# digidice_TI.net
KiCad netlist of a schematic drawn in EAGLE
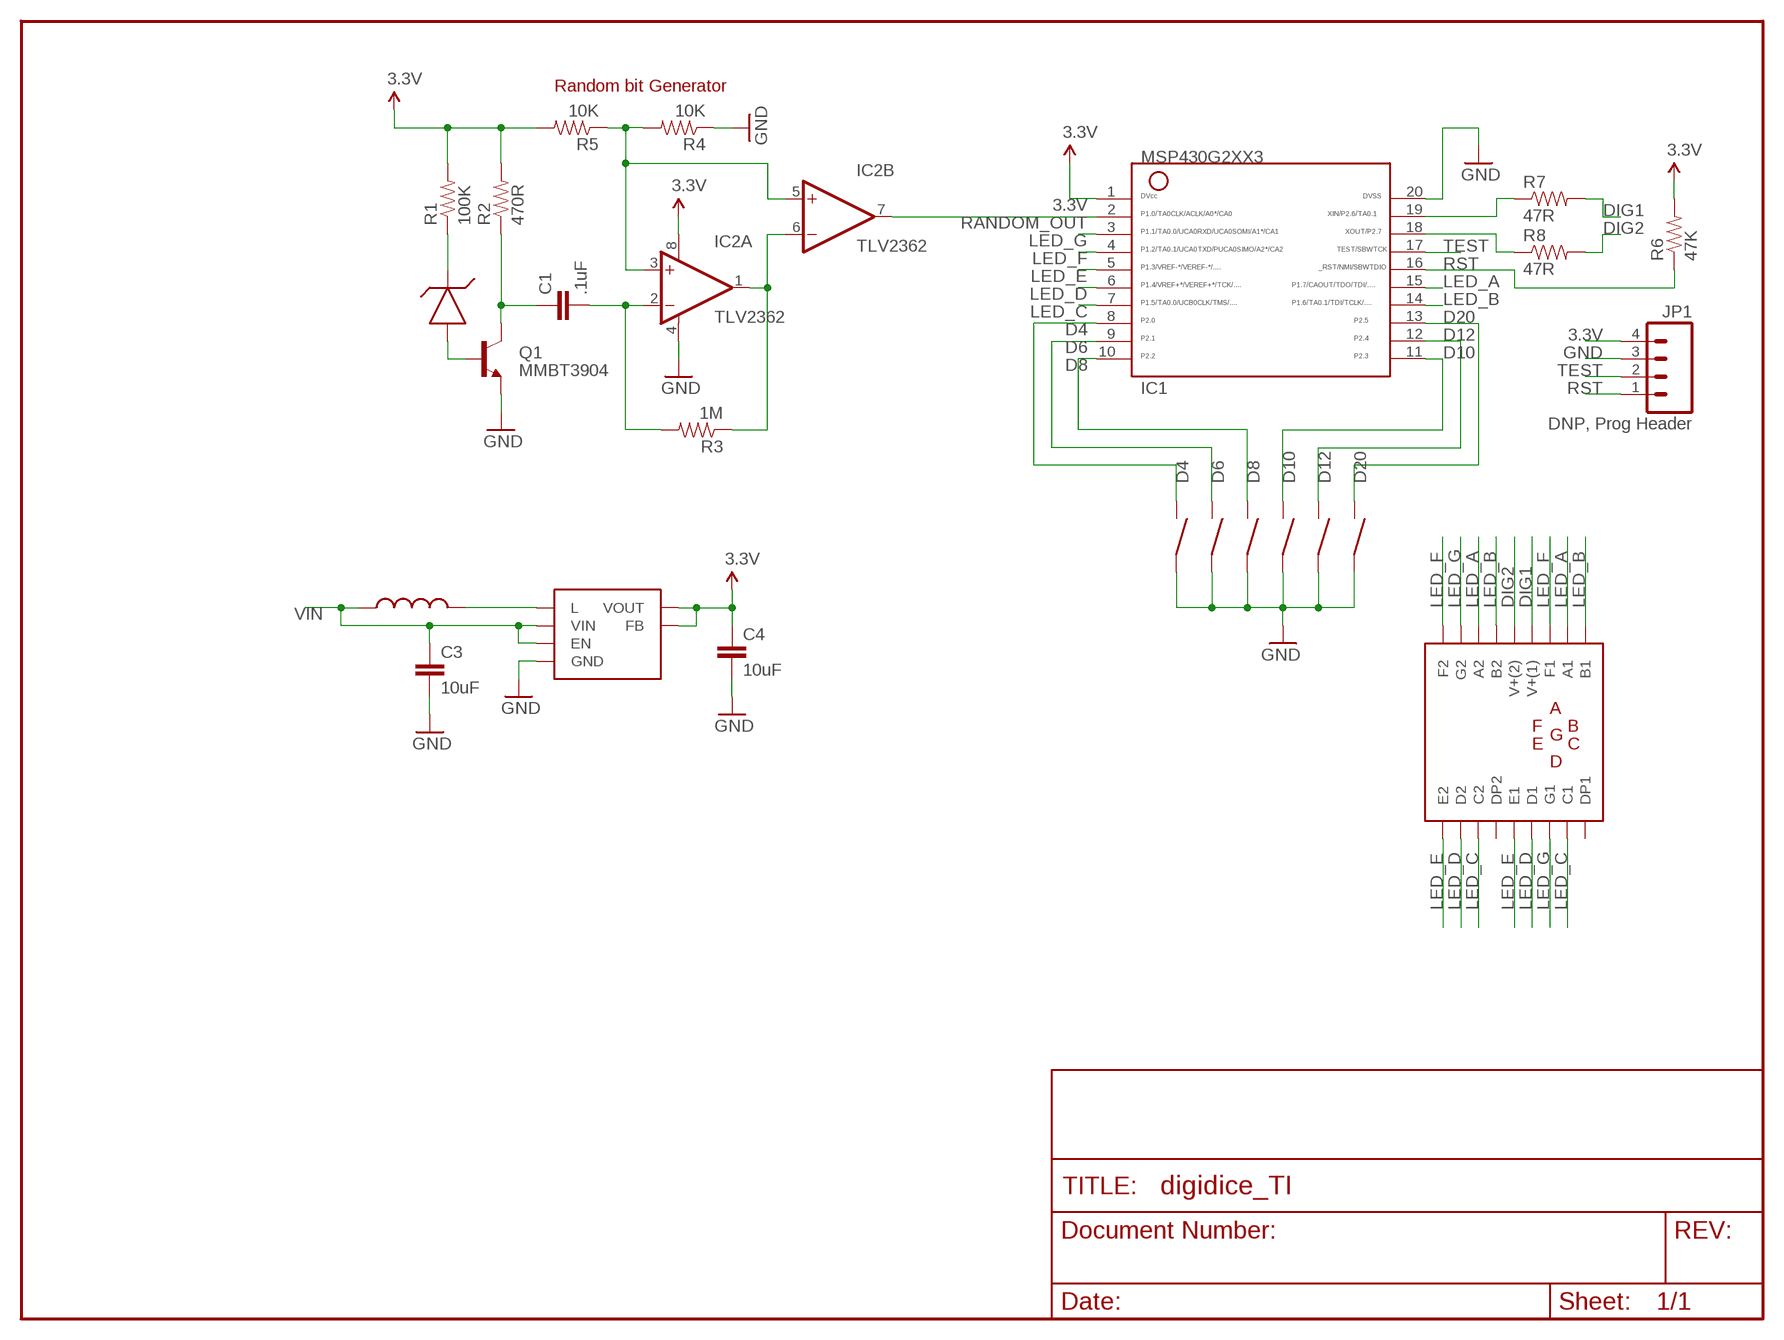
[diagram p0: schematic, sheet 1]

(export (version "E")
  (design (tool "Eeschema 10.0.6"))
  (components
    (comp (ref "C1")
      (value ".1uF")
      (footprint "eagle-import:0402-CAP")
      (libsource (lib "eagle-import") (part "CAP0402-CAP"))
    )
    (comp (ref "C3")
      (value "10uF")
      (footprint "eagle-import:0603-CAP")
      (libsource (lib "eagle-import") (part "CAP0603-CAP"))
    )
    (comp (ref "C4")
      (value "10uF")
      (footprint "eagle-import:0603-CAP")
      (libsource (lib "eagle-import") (part "CAP0603-CAP"))
    )
    (comp (ref "IC1")
      (value "MSP430G2203IPW20")
      (footprint "eagle-import:PW20")
      (libsource (lib "eagle-import") (part "G2XX3---PW20"))
    )
    (comp (ref "IC2")
      (value "TLV2362")
      (footprint "eagle-import:MSOP08")
      (fields
        (field (name "MF") "TEXAS INSTRUMENTS")
        (field (name "MPN") "OPA2340EA/250")
        (field (name "MPN_1") "OPA2340EA/250")
        (field (name "OC_FARNELL") "1101540")
        (field (name "OC_NEWARK") "36K7580")
      )
      (libsource (lib "eagle-import") (part "OPA2340E"))
    )
    (comp (ref "IC3")
      (value "TLV61225")
      (footprint "eagle-import:SOT-363")
      (libsource (lib "eagle-import") (part "TLV61225"))
    )
    (comp (ref "JP1")
      (value "DNP, Prog Header")
      (footprint "eagle-import:1X04-1.27MM")
      (libsource (lib "eagle-import") (part "M041.27MM"))
    )
    (comp (ref "L1")
      (value "PFL2015-472ML")
      (footprint "eagle-import:COILCRAFT-PFL2015")
      (libsource (lib "eagle-import") (part "INDUCTORPFL2015"))
    )
    (comp (ref "Q1")
      (value "MMBT3904")
      (footprint "eagle-import:SOT23")
      (libsource (lib "eagle-import") (part "TRANSISTOR_NPNSOT23"))
    )
    (comp (ref "R1")
      (value "100K")
      (footprint "eagle-import:0402-RES")
      (libsource (lib "eagle-import") (part "RESISTOR0402-RES"))
    )
    (comp (ref "R2")
      (value "470R")
      (footprint "eagle-import:0402-RES")
      (libsource (lib "eagle-import") (part "RESISTOR0402-RES"))
    )
    (comp (ref "R3")
      (value "1M")
      (footprint "eagle-import:0402-RES")
      (libsource (lib "eagle-import") (part "RESISTOR0402-RES"))
    )
    (comp (ref "R4")
      (value "10K")
      (footprint "eagle-import:0402-RES")
      (libsource (lib "eagle-import") (part "RESISTOR0402-RES"))
    )
    (comp (ref "R5")
      (value "10K")
      (footprint "eagle-import:0402-RES")
      (libsource (lib "eagle-import") (part "RESISTOR0402-RES"))
    )
    (comp (ref "R6")
      (value "47K")
      (footprint "eagle-import:0402-RES")
      (libsource (lib "eagle-import") (part "RESISTOR0402-RES"))
    )
    (comp (ref "R7")
      (value "47R")
      (footprint "eagle-import:0805")
      (libsource (lib "eagle-import") (part "RESISTOR"))
    )
    (comp (ref "R8")
      (value "47R")
      (footprint "eagle-import:0805")
      (libsource (lib "eagle-import") (part "RESISTOR"))
    )
    (comp (ref "SW1")
      (value "SPST_SWITCH")
      (footprint "eagle-import:EG2513-ND")
      (libsource (lib "eagle-import") (part "SPST_SWITCH"))
    )
    (comp (ref "SW2")
      (value "SPST_SWITCH")
      (footprint "eagle-import:EG2513-ND")
      (libsource (lib "eagle-import") (part "SPST_SWITCH"))
    )
    (comp (ref "SW3")
      (value "SPST_SWITCH")
      (footprint "eagle-import:EG2513-ND")
      (libsource (lib "eagle-import") (part "SPST_SWITCH"))
    )
    (comp (ref "SW4")
      (value "SPST_SWITCH")
      (footprint "eagle-import:EG2513-ND")
      (libsource (lib "eagle-import") (part "SPST_SWITCH"))
    )
    (comp (ref "SW5")
      (value "SPST_SWITCH")
      (footprint "eagle-import:EG2513-ND")
      (libsource (lib "eagle-import") (part "SPST_SWITCH"))
    )
    (comp (ref "SW6")
      (value "SPST_SWITCH")
      (footprint "eagle-import:EG2513-ND")
      (libsource (lib "eagle-import") (part "SPST_SWITCH"))
    )
    (comp (ref "U$1")
      (value "ZXRE1004FFTA")
      (footprint "eagle-import:SOT23")
      (libsource (lib "eagle-import") (part "ZXRE1004FFTA"))
    )
    (comp (ref "U$2")
      (value "2DIGIT_7SEGMENT")
      (footprint "eagle-import:HDSP-521E")
      (libsource (lib "eagle-import") (part "2DIGIT_7SEGMENT"))
    )
  )
  (nets
    (net (code "1") (name "/D4") (class "Default")
      (node (ref "IC1") (pin "8") (pinfunction "8_8") (pintype "bidirectional"))
      (node (ref "SW6") (pin "P$2") (pinfunction "2_P$2") (pintype "bidirectional"))
    )
    (net (code "2") (name "/D6") (class "Default")
      (node (ref "IC1") (pin "9") (pinfunction "9_9") (pintype "bidirectional"))
      (node (ref "SW5") (pin "P$2") (pinfunction "2_P$2") (pintype "bidirectional"))
    )
    (net (code "3") (name "/D8") (class "Default")
      (node (ref "IC1") (pin "10") (pinfunction "10_10") (pintype "bidirectional"))
      (node (ref "SW4") (pin "P$2") (pinfunction "2_P$2") (pintype "bidirectional"))
    )
    (net (code "4") (name "/D10") (class "Default")
      (node (ref "IC1") (pin "11") (pinfunction "11_11") (pintype "bidirectional"))
      (node (ref "SW3") (pin "P$2") (pinfunction "2_P$2") (pintype "bidirectional"))
    )
    (net (code "5") (name "/D12") (class "Default")
      (node (ref "IC1") (pin "12") (pinfunction "12_12") (pintype "bidirectional"))
      (node (ref "SW2") (pin "P$2") (pinfunction "2_P$2") (pintype "bidirectional"))
    )
    (net (code "6") (name "/D20") (class "Default")
      (node (ref "IC1") (pin "13") (pinfunction "13_13") (pintype "bidirectional"))
      (node (ref "SW1") (pin "P$2") (pinfunction "2_P$2") (pintype "bidirectional"))
    )
    (net (code "7") (name "/DIG1") (class "Default")
      (node (ref "R7") (pin "2") (pinfunction "2_2") (pintype "passive"))
      (node (ref "U$2") (pin "P$13") (pinfunction "V+(1)_P$13") (pintype "bidirectional"))
    )
    (net (code "8") (name "/DIG2") (class "Default")
      (node (ref "R8") (pin "2") (pinfunction "2_2") (pintype "passive"))
      (node (ref "U$2") (pin "P$14") (pinfunction "V+(2)_P$14") (pintype "bidirectional"))
    )
    (net (code "9") (name "/LED_A") (class "Default")
      (node (ref "IC1") (pin "15") (pinfunction "15_15") (pintype "bidirectional"))
      (node (ref "U$2") (pin "P$11") (pinfunction "A1_P$11") (pintype "bidirectional"))
      (node (ref "U$2") (pin "P$16") (pinfunction "A2_P$16") (pintype "bidirectional"))
    )
    (net (code "10") (name "/LED_B") (class "Default")
      (node (ref "IC1") (pin "14") (pinfunction "14_14") (pintype "bidirectional"))
      (node (ref "U$2") (pin "P$10") (pinfunction "B1_P$10") (pintype "bidirectional"))
      (node (ref "U$2") (pin "P$15") (pinfunction "B2_P$15") (pintype "bidirectional"))
    )
    (net (code "11") (name "/LED_C") (class "Default")
      (node (ref "IC1") (pin "7") (pinfunction "7_7") (pintype "bidirectional"))
      (node (ref "U$2") (pin "P$3") (pinfunction "C2_P$3") (pintype "bidirectional"))
      (node (ref "U$2") (pin "P$8") (pinfunction "C1_P$8") (pintype "bidirectional"))
    )
    (net (code "12") (name "/LED_D") (class "Default")
      (node (ref "IC1") (pin "6") (pinfunction "6_6") (pintype "bidirectional"))
      (node (ref "U$2") (pin "P$2") (pinfunction "D2_P$2") (pintype "bidirectional"))
      (node (ref "U$2") (pin "P$6") (pinfunction "D1_P$6") (pintype "bidirectional"))
    )
    (net (code "13") (name "/LED_E") (class "Default")
      (node (ref "IC1") (pin "5") (pinfunction "5_5") (pintype "bidirectional"))
      (node (ref "U$2") (pin "P$1") (pinfunction "E2_P$1") (pintype "bidirectional"))
      (node (ref "U$2") (pin "P$5") (pinfunction "E1_P$5") (pintype "bidirectional"))
    )
    (net (code "14") (name "/LED_F") (class "Default")
      (node (ref "IC1") (pin "4") (pinfunction "4_4") (pintype "bidirectional"))
      (node (ref "U$2") (pin "P$12") (pinfunction "F1_P$12") (pintype "bidirectional"))
      (node (ref "U$2") (pin "P$18") (pinfunction "F2_P$18") (pintype "bidirectional"))
    )
    (net (code "15") (name "/LED_G") (class "Default")
      (node (ref "IC1") (pin "3") (pinfunction "3_3") (pintype "bidirectional"))
      (node (ref "U$2") (pin "P$17") (pinfunction "G2_P$17") (pintype "bidirectional"))
      (node (ref "U$2") (pin "P$7") (pinfunction "G1_P$7") (pintype "bidirectional"))
    )
    (net (code "16") (name "/RANDOM_OUT") (class "Default")
      (node (ref "IC1") (pin "2") (pinfunction "2_2") (pintype "bidirectional"))
      (node (ref "IC2") (pin "7") (pinfunction "OUT_7") (pintype "output"))
    )
    (net (code "17") (name "/RST") (class "Default")
      (node (ref "IC1") (pin "16") (pinfunction "16_16") (pintype "bidirectional"))
      (node (ref "JP1") (pin "1") (pinfunction "1_1") (pintype "passive"))
      (node (ref "R6") (pin "1") (pinfunction "1_1") (pintype "passive"))
    )
    (net (code "18") (name "/TEST") (class "Default")
      (node (ref "IC1") (pin "17") (pinfunction "17_17") (pintype "bidirectional"))
      (node (ref "JP1") (pin "2") (pinfunction "2_2") (pintype "passive"))
    )
    (net (code "19") (name "/VIN") (class "Default")
      (node (ref "C3") (pin "1") (pinfunction "1_1") (pintype "passive"))
      (node (ref "IC3") (pin "P$1") (pinfunction "VIN_P$1") (pintype "bidirectional"))
      (node (ref "IC3") (pin "P$6") (pinfunction "EN_P$6") (pintype "bidirectional"))
      (node (ref "L1") (pin "P$1") (pinfunction "1_P$1") (pintype "bidirectional"))
    )
    (net (code "20") (name "3.3V") (class "Default")
      (node (ref "C4") (pin "1") (pinfunction "1_1") (pintype "passive"))
      (node (ref "IC1") (pin "1") (pinfunction "1_1") (pintype "bidirectional"))
      (node (ref "IC2") (pin "8") (pinfunction "V+_8") (pintype "power_in"))
      (node (ref "IC3") (pin "P$2") (pinfunction "FB_P$2") (pintype "bidirectional"))
      (node (ref "IC3") (pin "P$4") (pinfunction "VOUT_P$4") (pintype "bidirectional"))
      (node (ref "JP1") (pin "4") (pinfunction "4_4") (pintype "passive"))
      (node (ref "R1") (pin "2") (pinfunction "2_2") (pintype "passive"))
      (node (ref "R2") (pin "2") (pinfunction "2_2") (pintype "passive"))
      (node (ref "R5") (pin "2") (pinfunction "2_2") (pintype "passive"))
      (node (ref "R6") (pin "2") (pinfunction "2_2") (pintype "passive"))
    )
    (net (code "21") (name "GND") (class "Default")
      (node (ref "C3") (pin "2") (pinfunction "2_2") (pintype "passive"))
      (node (ref "C4") (pin "2") (pinfunction "2_2") (pintype "passive"))
      (node (ref "IC1") (pin "20") (pinfunction "20_20") (pintype "bidirectional"))
      (node (ref "IC2") (pin "4") (pinfunction "V-_4") (pintype "power_in"))
      (node (ref "IC3") (pin "P$3") (pinfunction "GND_P$3") (pintype "bidirectional"))
      (node (ref "JP1") (pin "3") (pinfunction "3_3") (pintype "passive"))
      (node (ref "Q1") (pin "2") (pinfunction "E_2") (pintype "passive"))
      (node (ref "R4") (pin "1") (pinfunction "1_1") (pintype "passive"))
      (node (ref "SW1") (pin "P$1") (pinfunction "1_P$1") (pintype "bidirectional"))
      (node (ref "SW2") (pin "P$1") (pinfunction "1_P$1") (pintype "bidirectional"))
      (node (ref "SW3") (pin "P$1") (pinfunction "1_P$1") (pintype "bidirectional"))
      (node (ref "SW4") (pin "P$1") (pinfunction "1_P$1") (pintype "bidirectional"))
      (node (ref "SW5") (pin "P$1") (pinfunction "1_P$1") (pintype "bidirectional"))
      (node (ref "SW6") (pin "P$1") (pinfunction "1_P$1") (pintype "bidirectional"))
    )
    (net (code "22") (name "Net-(IC1-Pad18)") (class "Default")
      (node (ref "IC1") (pin "18") (pinfunction "18_18") (pintype "bidirectional"))
      (node (ref "R8") (pin "1") (pinfunction "1_1") (pintype "passive"))
    )
    (net (code "23") (name "Net-(IC1-Pad19)") (class "Default")
      (node (ref "IC1") (pin "19") (pinfunction "19_19") (pintype "bidirectional"))
      (node (ref "R7") (pin "1") (pinfunction "1_1") (pintype "passive"))
    )
    (net (code "24") (name "Net-(IC2A-+IN)") (class "Default")
      (node (ref "IC2") (pin "3") (pinfunction "+IN_3") (pintype "input"))
      (node (ref "IC2") (pin "5") (pinfunction "+IN_5") (pintype "input"))
      (node (ref "R4") (pin "2") (pinfunction "2_2") (pintype "passive"))
      (node (ref "R5") (pin "1") (pinfunction "1_1") (pintype "passive"))
    )
    (net (code "25") (name "Net-(IC2A--IN)") (class "Default")
      (node (ref "C1") (pin "2") (pinfunction "2_2") (pintype "passive"))
      (node (ref "IC2") (pin "2") (pinfunction "-IN_2") (pintype "input"))
      (node (ref "R3") (pin "2") (pinfunction "2_2") (pintype "passive"))
    )
    (net (code "26") (name "Net-(IC2A-OUT)") (class "Default")
      (node (ref "IC2") (pin "1") (pinfunction "OUT_1") (pintype "output"))
      (node (ref "IC2") (pin "6") (pinfunction "-IN_6") (pintype "input"))
      (node (ref "R3") (pin "1") (pinfunction "1_1") (pintype "passive"))
    )
    (net (code "27") (name "Net-(IC3-L)") (class "Default")
      (node (ref "IC3") (pin "P$5") (pinfunction "L_P$5") (pintype "bidirectional"))
      (node (ref "L1") (pin "P$2") (pinfunction "2_P$2") (pintype "bidirectional"))
    )
    (net (code "28") (name "Net-(Q1-B)") (class "Default")
      (node (ref "Q1") (pin "1") (pinfunction "B_1") (pintype "passive"))
      (node (ref "U$1") (pin "2") (pinfunction "A_2") (pintype "bidirectional"))
    )
    (net (code "29") (name "Net-(Q1-C)") (class "Default")
      (node (ref "C1") (pin "1") (pinfunction "1_1") (pintype "passive"))
      (node (ref "Q1") (pin "3") (pinfunction "C_3") (pintype "passive"))
      (node (ref "R2") (pin "1") (pinfunction "1_1") (pintype "passive"))
    )
    (net (code "30") (name "Net-(U$1-K)") (class "Default")
      (node (ref "R1") (pin "1") (pinfunction "1_1") (pintype "passive"))
      (node (ref "U$1") (pin "1") (pinfunction "K_1") (pintype "bidirectional"))
    )
    (net (code "31") (name "unconnected-(U$2-DP1-PadP$9)") (class "Default")
      (node (ref "U$2") (pin "P$9") (pinfunction "DP1_P$9") (pintype "bidirectional"))
    )
    (net (code "32") (name "unconnected-(U$2-DP2-PadP$4)") (class "Default")
      (node (ref "U$2") (pin "P$4") (pinfunction "DP2_P$4") (pintype "bidirectional"))
    )
  )
)
